# TestBoard3.net
KiCad netlist of a schematic drawn in EAGLE
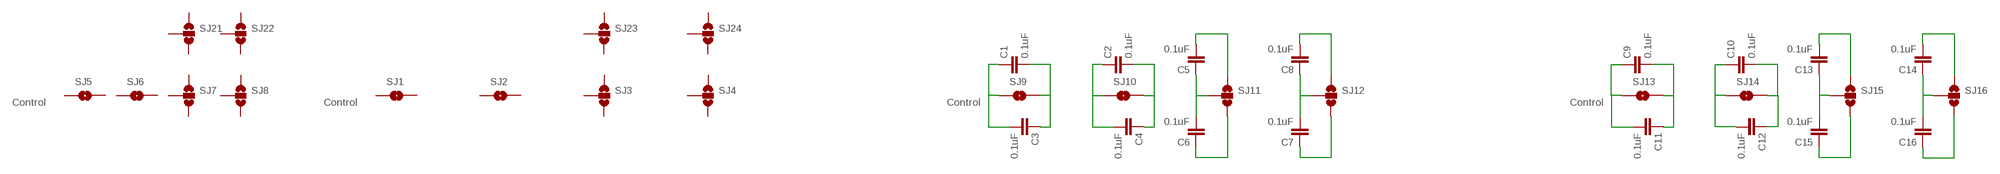
[diagram p0: schematic, sheet 1, part 1 of 3]
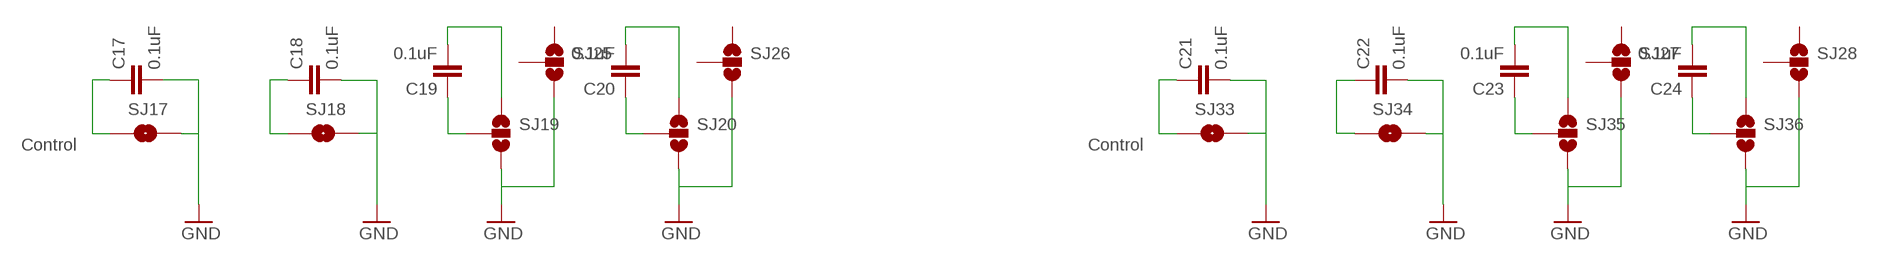
[diagram p1: schematic, sheet 1, part 2 of 3]
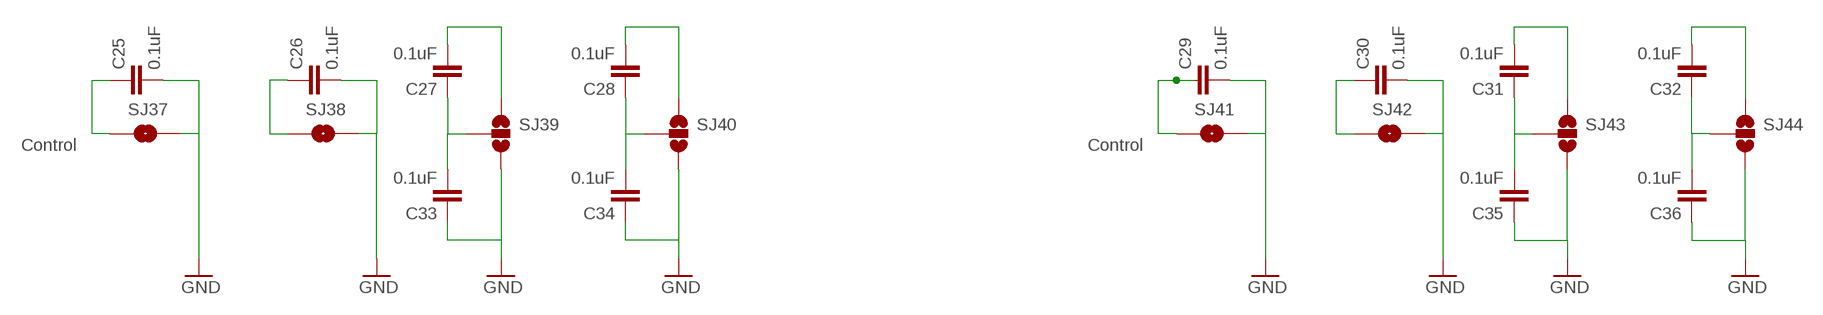
[diagram p2: schematic, sheet 1, part 3 of 3]

(export (version "E")
  (design (tool "Eeschema 10.0.6"))
  (components
    (comp (ref "C1")
      (value "0.1uF")
      (footprint "eagle-import:0603-CAP")
      (libsource (lib "eagle-import") (part "0.1UF-25V-5%(0603)"))
    )
    (comp (ref "C2")
      (value "0.1uF")
      (footprint "eagle-import:0603-CAP")
      (libsource (lib "eagle-import") (part "0.1UF-25V-5%(0603)"))
    )
    (comp (ref "C3")
      (value "0.1uF")
      (footprint "eagle-import:0603-CAP")
      (libsource (lib "eagle-import") (part "0.1UF-25V-5%(0603)"))
    )
    (comp (ref "C4")
      (value "0.1uF")
      (footprint "eagle-import:0603-CAP")
      (libsource (lib "eagle-import") (part "0.1UF-25V-5%(0603)"))
    )
    (comp (ref "C5")
      (value "0.1uF")
      (footprint "eagle-import:0603-CAP")
      (libsource (lib "eagle-import") (part "0.1UF-25V-5%(0603)"))
    )
    (comp (ref "C6")
      (value "0.1uF")
      (footprint "eagle-import:0603-CAP")
      (libsource (lib "eagle-import") (part "0.1UF-25V-5%(0603)"))
    )
    (comp (ref "C7")
      (value "0.1uF")
      (footprint "eagle-import:0603-CAP")
      (libsource (lib "eagle-import") (part "0.1UF-25V-5%(0603)"))
    )
    (comp (ref "C8")
      (value "0.1uF")
      (footprint "eagle-import:0603-CAP")
      (libsource (lib "eagle-import") (part "0.1UF-25V-5%(0603)"))
    )
    (comp (ref "C9")
      (value "0.1uF")
      (footprint "eagle-import:0603-CAP")
      (libsource (lib "eagle-import") (part "0.1UF-25V-5%(0603)"))
    )
    (comp (ref "C10")
      (value "0.1uF")
      (footprint "eagle-import:0603-CAP")
      (libsource (lib "eagle-import") (part "0.1UF-25V-5%(0603)"))
    )
    (comp (ref "C11")
      (value "0.1uF")
      (footprint "eagle-import:0603-CAP")
      (libsource (lib "eagle-import") (part "0.1UF-25V-5%(0603)"))
    )
    (comp (ref "C12")
      (value "0.1uF")
      (footprint "eagle-import:0603-CAP")
      (libsource (lib "eagle-import") (part "0.1UF-25V-5%(0603)"))
    )
    (comp (ref "C13")
      (value "0.1uF")
      (footprint "eagle-import:0603-CAP")
      (libsource (lib "eagle-import") (part "0.1UF-25V-5%(0603)"))
    )
    (comp (ref "C14")
      (value "0.1uF")
      (footprint "eagle-import:0603-CAP")
      (libsource (lib "eagle-import") (part "0.1UF-25V-5%(0603)"))
    )
    (comp (ref "C15")
      (value "0.1uF")
      (footprint "eagle-import:0603-CAP")
      (libsource (lib "eagle-import") (part "0.1UF-25V-5%(0603)"))
    )
    (comp (ref "C16")
      (value "0.1uF")
      (footprint "eagle-import:0603-CAP")
      (libsource (lib "eagle-import") (part "0.1UF-25V-5%(0603)"))
    )
    (comp (ref "C17")
      (value "0.1uF")
      (footprint "eagle-import:0603-CAP")
      (libsource (lib "eagle-import") (part "0.1UF-25V-5%(0603)"))
    )
    (comp (ref "C18")
      (value "0.1uF")
      (footprint "eagle-import:0603-CAP")
      (libsource (lib "eagle-import") (part "0.1UF-25V-5%(0603)"))
    )
    (comp (ref "C19")
      (value "0.1uF")
      (footprint "eagle-import:0603-CAP")
      (libsource (lib "eagle-import") (part "0.1UF-25V-5%(0603)"))
    )
    (comp (ref "C20")
      (value "0.1uF")
      (footprint "eagle-import:0603-CAP")
      (libsource (lib "eagle-import") (part "0.1UF-25V-5%(0603)"))
    )
    (comp (ref "C21")
      (value "0.1uF")
      (footprint "eagle-import:0603-CAP")
      (libsource (lib "eagle-import") (part "0.1UF-25V-5%(0603)"))
    )
    (comp (ref "C22")
      (value "0.1uF")
      (footprint "eagle-import:0603-CAP")
      (libsource (lib "eagle-import") (part "0.1UF-25V-5%(0603)"))
    )
    (comp (ref "C23")
      (value "0.1uF")
      (footprint "eagle-import:0603-CAP")
      (libsource (lib "eagle-import") (part "0.1UF-25V-5%(0603)"))
    )
    (comp (ref "C24")
      (value "0.1uF")
      (footprint "eagle-import:0603-CAP")
      (libsource (lib "eagle-import") (part "0.1UF-25V-5%(0603)"))
    )
    (comp (ref "C25")
      (value "0.1uF")
      (footprint "eagle-import:0603-CAP")
      (libsource (lib "eagle-import") (part "0.1UF-25V-5%(0603)"))
    )
    (comp (ref "C26")
      (value "0.1uF")
      (footprint "eagle-import:0603-CAP")
      (libsource (lib "eagle-import") (part "0.1UF-25V-5%(0603)"))
    )
    (comp (ref "C27")
      (value "0.1uF")
      (footprint "eagle-import:0603-CAP")
      (libsource (lib "eagle-import") (part "0.1UF-25V-5%(0603)"))
    )
    (comp (ref "C28")
      (value "0.1uF")
      (footprint "eagle-import:0603-CAP")
      (libsource (lib "eagle-import") (part "0.1UF-25V-5%(0603)"))
    )
    (comp (ref "C29")
      (value "0.1uF")
      (footprint "eagle-import:0603-CAP")
      (libsource (lib "eagle-import") (part "0.1UF-25V-5%(0603)"))
    )
    (comp (ref "C30")
      (value "0.1uF")
      (footprint "eagle-import:0603-CAP")
      (libsource (lib "eagle-import") (part "0.1UF-25V-5%(0603)"))
    )
    (comp (ref "C31")
      (value "0.1uF")
      (footprint "eagle-import:0603-CAP")
      (libsource (lib "eagle-import") (part "0.1UF-25V-5%(0603)"))
    )
    (comp (ref "C32")
      (value "0.1uF")
      (footprint "eagle-import:0603-CAP")
      (libsource (lib "eagle-import") (part "0.1UF-25V-5%(0603)"))
    )
    (comp (ref "C33")
      (value "0.1uF")
      (footprint "eagle-import:0603-CAP")
      (libsource (lib "eagle-import") (part "0.1UF-25V-5%(0603)"))
    )
    (comp (ref "C34")
      (value "0.1uF")
      (footprint "eagle-import:0603-CAP")
      (libsource (lib "eagle-import") (part "0.1UF-25V-5%(0603)"))
    )
    (comp (ref "C35")
      (value "0.1uF")
      (footprint "eagle-import:0603-CAP")
      (libsource (lib "eagle-import") (part "0.1UF-25V-5%(0603)"))
    )
    (comp (ref "C36")
      (value "0.1uF")
      (footprint "eagle-import:0603-CAP")
      (libsource (lib "eagle-import") (part "0.1UF-25V-5%(0603)"))
    )
    (comp (ref "SJ1")
      (value "JUMPER-PAD-2-NO")
      (footprint "eagle-import:PAD-JUMPER-2-NO_NO_SILK")
      (libsource (lib "eagle-import") (part "JUMPER-PAD-2-NO"))
    )
    (comp (ref "SJ2")
      (value "JUMPER-PAD-2-NO")
      (footprint "eagle-import:PAD-JUMPER-2-NO_NO_SILK")
      (libsource (lib "eagle-import") (part "JUMPER-PAD-2-NO"))
    )
    (comp (ref "SJ3")
      (value "JUMPER-PAD-3-NOYES_SILK")
      (footprint "eagle-import:PAD-JUMPER-3-NO_YES_SILK")
      (libsource (lib "eagle-import") (part "JUMPER-PAD-3-NOYES_SILK"))
    )
    (comp (ref "SJ4")
      (value "JUMPER-PAD-3-NOYES_SILK")
      (footprint "eagle-import:PAD-JUMPER-3-NO_YES_SILK")
      (libsource (lib "eagle-import") (part "JUMPER-PAD-3-NOYES_SILK"))
    )
    (comp (ref "SJ5")
      (value "JUMPER-PAD-2-NO")
      (footprint "eagle-import:PAD-JUMPER-2-NO_NO_SILK")
      (libsource (lib "eagle-import") (part "JUMPER-PAD-2-NO"))
    )
    (comp (ref "SJ6")
      (value "JUMPER-PAD-2-NO")
      (footprint "eagle-import:PAD-JUMPER-2-NO_NO_SILK")
      (libsource (lib "eagle-import") (part "JUMPER-PAD-2-NO"))
    )
    (comp (ref "SJ7")
      (value "JUMPER-PAD-3-NOYES_SILK")
      (footprint "eagle-import:PAD-JUMPER-3-NO_YES_SILK")
      (libsource (lib "eagle-import") (part "JUMPER-PAD-3-NOYES_SILK"))
    )
    (comp (ref "SJ8")
      (value "JUMPER-PAD-3-NOYES_SILK")
      (footprint "eagle-import:PAD-JUMPER-3-NO_YES_SILK")
      (libsource (lib "eagle-import") (part "JUMPER-PAD-3-NOYES_SILK"))
    )
    (comp (ref "SJ9")
      (value "JUMPER-PAD-2-NO")
      (footprint "eagle-import:PAD-JUMPER-2-NO_NO_SILK")
      (libsource (lib "eagle-import") (part "JUMPER-PAD-2-NO"))
    )
    (comp (ref "SJ10")
      (value "JUMPER-PAD-2-NO")
      (footprint "eagle-import:PAD-JUMPER-2-NO_NO_SILK")
      (libsource (lib "eagle-import") (part "JUMPER-PAD-2-NO"))
    )
    (comp (ref "SJ11")
      (value "JUMPER-PAD-3-NOYES_SILK")
      (footprint "eagle-import:PAD-JUMPER-3-NO_YES_SILK")
      (libsource (lib "eagle-import") (part "JUMPER-PAD-3-NOYES_SILK"))
    )
    (comp (ref "SJ12")
      (value "JUMPER-PAD-3-NOYES_SILK")
      (footprint "eagle-import:PAD-JUMPER-3-NO_YES_SILK")
      (libsource (lib "eagle-import") (part "JUMPER-PAD-3-NOYES_SILK"))
    )
    (comp (ref "SJ13")
      (value "JUMPER-PAD-2-NO")
      (footprint "eagle-import:PAD-JUMPER-2-NO_NO_SILK")
      (libsource (lib "eagle-import") (part "JUMPER-PAD-2-NO"))
    )
    (comp (ref "SJ14")
      (value "JUMPER-PAD-2-NO")
      (footprint "eagle-import:PAD-JUMPER-2-NO_NO_SILK")
      (libsource (lib "eagle-import") (part "JUMPER-PAD-2-NO"))
    )
    (comp (ref "SJ15")
      (value "JUMPER-PAD-3-NOYES_SILK")
      (footprint "eagle-import:PAD-JUMPER-3-NO_YES_SILK")
      (libsource (lib "eagle-import") (part "JUMPER-PAD-3-NOYES_SILK"))
    )
    (comp (ref "SJ16")
      (value "JUMPER-PAD-3-NOYES_SILK")
      (footprint "eagle-import:PAD-JUMPER-3-NO_YES_SILK")
      (libsource (lib "eagle-import") (part "JUMPER-PAD-3-NOYES_SILK"))
    )
    (comp (ref "SJ17")
      (value "JUMPER-PAD-2-NO")
      (footprint "eagle-import:PAD-JUMPER-2-NO_NO_SILK")
      (libsource (lib "eagle-import") (part "JUMPER-PAD-2-NO"))
    )
    (comp (ref "SJ18")
      (value "JUMPER-PAD-2-NO")
      (footprint "eagle-import:PAD-JUMPER-2-NO_NO_SILK")
      (libsource (lib "eagle-import") (part "JUMPER-PAD-2-NO"))
    )
    (comp (ref "SJ19")
      (value "JUMPER-PAD-3-NOYES_SILK")
      (footprint "eagle-import:PAD-JUMPER-3-NO_YES_SILK")
      (libsource (lib "eagle-import") (part "JUMPER-PAD-3-NOYES_SILK"))
    )
    (comp (ref "SJ20")
      (value "JUMPER-PAD-3-NOYES_SILK")
      (footprint "eagle-import:PAD-JUMPER-3-NO_YES_SILK")
      (libsource (lib "eagle-import") (part "JUMPER-PAD-3-NOYES_SILK"))
    )
    (comp (ref "SJ21")
      (value "JUMPER-PAD-3-NOYES_SILK")
      (footprint "eagle-import:PAD-JUMPER-3-NO_YES_SILK")
      (libsource (lib "eagle-import") (part "JUMPER-PAD-3-NOYES_SILK"))
    )
    (comp (ref "SJ22")
      (value "JUMPER-PAD-3-NOYES_SILK")
      (footprint "eagle-import:PAD-JUMPER-3-NO_YES_SILK")
      (libsource (lib "eagle-import") (part "JUMPER-PAD-3-NOYES_SILK"))
    )
    (comp (ref "SJ23")
      (value "JUMPER-PAD-3-NOYES_SILK")
      (footprint "eagle-import:PAD-JUMPER-3-NO_YES_SILK")
      (libsource (lib "eagle-import") (part "JUMPER-PAD-3-NOYES_SILK"))
    )
    (comp (ref "SJ24")
      (value "JUMPER-PAD-3-NOYES_SILK")
      (footprint "eagle-import:PAD-JUMPER-3-NO_YES_SILK")
      (libsource (lib "eagle-import") (part "JUMPER-PAD-3-NOYES_SILK"))
    )
    (comp (ref "SJ25")
      (value "JUMPER-PAD-3-NOYES_SILK")
      (footprint "eagle-import:PAD-JUMPER-3-NO_YES_SILK")
      (libsource (lib "eagle-import") (part "JUMPER-PAD-3-NOYES_SILK"))
    )
    (comp (ref "SJ26")
      (value "JUMPER-PAD-3-NOYES_SILK")
      (footprint "eagle-import:PAD-JUMPER-3-NO_YES_SILK")
      (libsource (lib "eagle-import") (part "JUMPER-PAD-3-NOYES_SILK"))
    )
    (comp (ref "SJ27")
      (value "JUMPER-PAD-3-NOYES_SILK")
      (footprint "eagle-import:PAD-JUMPER-3-NO_YES_SILK")
      (libsource (lib "eagle-import") (part "JUMPER-PAD-3-NOYES_SILK"))
    )
    (comp (ref "SJ28")
      (value "JUMPER-PAD-3-NOYES_SILK")
      (footprint "eagle-import:PAD-JUMPER-3-NO_YES_SILK")
      (libsource (lib "eagle-import") (part "JUMPER-PAD-3-NOYES_SILK"))
    )
    (comp (ref "SJ33")
      (value "JUMPER-PAD-2-NO")
      (footprint "eagle-import:PAD-JUMPER-2-NO_NO_SILK")
      (libsource (lib "eagle-import") (part "JUMPER-PAD-2-NO"))
    )
    (comp (ref "SJ34")
      (value "JUMPER-PAD-2-NO")
      (footprint "eagle-import:PAD-JUMPER-2-NO_NO_SILK")
      (libsource (lib "eagle-import") (part "JUMPER-PAD-2-NO"))
    )
    (comp (ref "SJ35")
      (value "JUMPER-PAD-3-NOYES_SILK")
      (footprint "eagle-import:PAD-JUMPER-3-NO_YES_SILK")
      (libsource (lib "eagle-import") (part "JUMPER-PAD-3-NOYES_SILK"))
    )
    (comp (ref "SJ36")
      (value "JUMPER-PAD-3-NOYES_SILK")
      (footprint "eagle-import:PAD-JUMPER-3-NO_YES_SILK")
      (libsource (lib "eagle-import") (part "JUMPER-PAD-3-NOYES_SILK"))
    )
    (comp (ref "SJ37")
      (value "JUMPER-PAD-2-NO")
      (footprint "eagle-import:PAD-JUMPER-2-NO_NO_SILK")
      (libsource (lib "eagle-import") (part "JUMPER-PAD-2-NO"))
    )
    (comp (ref "SJ38")
      (value "JUMPER-PAD-2-NO")
      (footprint "eagle-import:PAD-JUMPER-2-NO_NO_SILK")
      (libsource (lib "eagle-import") (part "JUMPER-PAD-2-NO"))
    )
    (comp (ref "SJ39")
      (value "JUMPER-PAD-3-NOYES_SILK")
      (footprint "eagle-import:PAD-JUMPER-3-NO_YES_SILK")
      (libsource (lib "eagle-import") (part "JUMPER-PAD-3-NOYES_SILK"))
    )
    (comp (ref "SJ40")
      (value "JUMPER-PAD-3-NOYES_SILK")
      (footprint "eagle-import:PAD-JUMPER-3-NO_YES_SILK")
      (libsource (lib "eagle-import") (part "JUMPER-PAD-3-NOYES_SILK"))
    )
    (comp (ref "SJ41")
      (value "JUMPER-PAD-2-NO")
      (footprint "eagle-import:PAD-JUMPER-2-NO_NO_SILK")
      (libsource (lib "eagle-import") (part "JUMPER-PAD-2-NO"))
    )
    (comp (ref "SJ42")
      (value "JUMPER-PAD-2-NO")
      (footprint "eagle-import:PAD-JUMPER-2-NO_NO_SILK")
      (libsource (lib "eagle-import") (part "JUMPER-PAD-2-NO"))
    )
    (comp (ref "SJ43")
      (value "JUMPER-PAD-3-NOYES_SILK")
      (footprint "eagle-import:PAD-JUMPER-3-NO_YES_SILK")
      (libsource (lib "eagle-import") (part "JUMPER-PAD-3-NOYES_SILK"))
    )
    (comp (ref "SJ44")
      (value "JUMPER-PAD-3-NOYES_SILK")
      (footprint "eagle-import:PAD-JUMPER-3-NO_YES_SILK")
      (libsource (lib "eagle-import") (part "JUMPER-PAD-3-NOYES_SILK"))
    )
  )
  (nets
    (net (code "1") (name "GND") (class "Default")
      (node (ref "C17") (pin "2") (pinfunction "2_2") (pintype "passive"))
      (node (ref "C18") (pin "2") (pinfunction "2_2") (pintype "passive"))
      (node (ref "C21") (pin "2") (pinfunction "2_2") (pintype "passive"))
      (node (ref "C22") (pin "2") (pinfunction "2_2") (pintype "passive"))
      (node (ref "C25") (pin "2") (pinfunction "2_2") (pintype "passive"))
      (node (ref "C26") (pin "2") (pinfunction "2_2") (pintype "passive"))
      (node (ref "C29") (pin "2") (pinfunction "2_2") (pintype "passive"))
      (node (ref "C30") (pin "2") (pinfunction "2_2") (pintype "passive"))
      (node (ref "C33") (pin "1") (pinfunction "1_1") (pintype "passive"))
      (node (ref "C34") (pin "1") (pinfunction "1_1") (pintype "passive"))
      (node (ref "C35") (pin "1") (pinfunction "1_1") (pintype "passive"))
      (node (ref "C36") (pin "1") (pinfunction "1_1") (pintype "passive"))
      (node (ref "SJ17") (pin "2") (pinfunction "2_2") (pintype "passive"))
      (node (ref "SJ18") (pin "2") (pinfunction "2_2") (pintype "passive"))
      (node (ref "SJ19") (pin "3") (pinfunction "3_3") (pintype "passive"))
      (node (ref "SJ20") (pin "3") (pinfunction "3_3") (pintype "passive"))
      (node (ref "SJ25") (pin "3") (pinfunction "3_3") (pintype "passive"))
      (node (ref "SJ26") (pin "3") (pinfunction "3_3") (pintype "passive"))
      (node (ref "SJ27") (pin "3") (pinfunction "3_3") (pintype "passive"))
      (node (ref "SJ28") (pin "3") (pinfunction "3_3") (pintype "passive"))
      (node (ref "SJ33") (pin "2") (pinfunction "2_2") (pintype "passive"))
      (node (ref "SJ34") (pin "2") (pinfunction "2_2") (pintype "passive"))
      (node (ref "SJ35") (pin "3") (pinfunction "3_3") (pintype "passive"))
      (node (ref "SJ36") (pin "3") (pinfunction "3_3") (pintype "passive"))
      (node (ref "SJ37") (pin "2") (pinfunction "2_2") (pintype "passive"))
      (node (ref "SJ38") (pin "2") (pinfunction "2_2") (pintype "passive"))
      (node (ref "SJ39") (pin "3") (pinfunction "3_3") (pintype "passive"))
      (node (ref "SJ40") (pin "3") (pinfunction "3_3") (pintype "passive"))
      (node (ref "SJ41") (pin "2") (pinfunction "2_2") (pintype "passive"))
      (node (ref "SJ42") (pin "2") (pinfunction "2_2") (pintype "passive"))
      (node (ref "SJ43") (pin "3") (pinfunction "3_3") (pintype "passive"))
      (node (ref "SJ44") (pin "3") (pinfunction "3_3") (pintype "passive"))
    )
    (net (code "2") (name "Net-(C1-Pad1)") (class "Default")
      (node (ref "C1") (pin "1") (pinfunction "1_1") (pintype "passive"))
      (node (ref "C3") (pin "2") (pinfunction "2_2") (pintype "passive"))
      (node (ref "SJ9") (pin "1") (pinfunction "1_1") (pintype "passive"))
    )
    (net (code "3") (name "Net-(C1-Pad2)") (class "Default")
      (node (ref "C1") (pin "2") (pinfunction "2_2") (pintype "passive"))
      (node (ref "C3") (pin "1") (pinfunction "1_1") (pintype "passive"))
      (node (ref "SJ9") (pin "2") (pinfunction "2_2") (pintype "passive"))
    )
    (net (code "4") (name "Net-(C2-Pad1)") (class "Default")
      (node (ref "C2") (pin "1") (pinfunction "1_1") (pintype "passive"))
      (node (ref "C4") (pin "2") (pinfunction "2_2") (pintype "passive"))
      (node (ref "SJ10") (pin "1") (pinfunction "1_1") (pintype "passive"))
    )
    (net (code "5") (name "Net-(C2-Pad2)") (class "Default")
      (node (ref "C2") (pin "2") (pinfunction "2_2") (pintype "passive"))
      (node (ref "C4") (pin "1") (pinfunction "1_1") (pintype "passive"))
      (node (ref "SJ10") (pin "2") (pinfunction "2_2") (pintype "passive"))
    )
    (net (code "6") (name "Net-(C5-Pad1)") (class "Default")
      (node (ref "C5") (pin "1") (pinfunction "1_1") (pintype "passive"))
      (node (ref "C6") (pin "2") (pinfunction "2_2") (pintype "passive"))
      (node (ref "SJ11") (pin "2") (pinfunction "2_2") (pintype "passive"))
    )
    (net (code "7") (name "Net-(C5-Pad2)") (class "Default")
      (node (ref "C5") (pin "2") (pinfunction "2_2") (pintype "passive"))
      (node (ref "SJ11") (pin "1") (pinfunction "1_1") (pintype "passive"))
    )
    (net (code "8") (name "Net-(C6-Pad1)") (class "Default")
      (node (ref "C6") (pin "1") (pinfunction "1_1") (pintype "passive"))
      (node (ref "SJ11") (pin "3") (pinfunction "3_3") (pintype "passive"))
    )
    (net (code "9") (name "Net-(C7-Pad1)") (class "Default")
      (node (ref "C7") (pin "1") (pinfunction "1_1") (pintype "passive"))
      (node (ref "SJ12") (pin "3") (pinfunction "3_3") (pintype "passive"))
    )
    (net (code "10") (name "Net-(C7-Pad2)") (class "Default")
      (node (ref "C7") (pin "2") (pinfunction "2_2") (pintype "passive"))
      (node (ref "C8") (pin "1") (pinfunction "1_1") (pintype "passive"))
      (node (ref "SJ12") (pin "2") (pinfunction "2_2") (pintype "passive"))
    )
    (net (code "11") (name "Net-(C8-Pad2)") (class "Default")
      (node (ref "C8") (pin "2") (pinfunction "2_2") (pintype "passive"))
      (node (ref "SJ12") (pin "1") (pinfunction "1_1") (pintype "passive"))
    )
    (net (code "12") (name "Net-(C10-Pad1)") (class "Default")
      (node (ref "C10") (pin "1") (pinfunction "1_1") (pintype "passive"))
      (node (ref "C12") (pin "2") (pinfunction "2_2") (pintype "passive"))
      (node (ref "SJ14") (pin "1") (pinfunction "1_1") (pintype "passive"))
    )
    (net (code "13") (name "Net-(C10-Pad2)") (class "Default")
      (node (ref "C10") (pin "2") (pinfunction "2_2") (pintype "passive"))
      (node (ref "C12") (pin "1") (pinfunction "1_1") (pintype "passive"))
      (node (ref "SJ14") (pin "2") (pinfunction "2_2") (pintype "passive"))
    )
    (net (code "14") (name "Net-(C11-Pad1)") (class "Default")
      (node (ref "C11") (pin "1") (pinfunction "1_1") (pintype "passive"))
      (node (ref "C9") (pin "2") (pinfunction "2_2") (pintype "passive"))
      (node (ref "SJ13") (pin "2") (pinfunction "2_2") (pintype "passive"))
    )
    (net (code "15") (name "Net-(C11-Pad2)") (class "Default")
      (node (ref "C11") (pin "2") (pinfunction "2_2") (pintype "passive"))
      (node (ref "C9") (pin "1") (pinfunction "1_1") (pintype "passive"))
      (node (ref "SJ13") (pin "1") (pinfunction "1_1") (pintype "passive"))
    )
    (net (code "16") (name "Net-(C13-Pad1)") (class "Default")
      (node (ref "C13") (pin "1") (pinfunction "1_1") (pintype "passive"))
      (node (ref "C15") (pin "2") (pinfunction "2_2") (pintype "passive"))
      (node (ref "SJ15") (pin "2") (pinfunction "2_2") (pintype "passive"))
    )
    (net (code "17") (name "Net-(C13-Pad2)") (class "Default")
      (node (ref "C13") (pin "2") (pinfunction "2_2") (pintype "passive"))
      (node (ref "SJ15") (pin "1") (pinfunction "1_1") (pintype "passive"))
    )
    (net (code "18") (name "Net-(C14-Pad1)") (class "Default")
      (node (ref "C14") (pin "1") (pinfunction "1_1") (pintype "passive"))
      (node (ref "C16") (pin "2") (pinfunction "2_2") (pintype "passive"))
      (node (ref "SJ16") (pin "2") (pinfunction "2_2") (pintype "passive"))
    )
    (net (code "19") (name "Net-(C14-Pad2)") (class "Default")
      (node (ref "C14") (pin "2") (pinfunction "2_2") (pintype "passive"))
      (node (ref "SJ16") (pin "1") (pinfunction "1_1") (pintype "passive"))
    )
    (net (code "20") (name "Net-(C15-Pad1)") (class "Default")
      (node (ref "C15") (pin "1") (pinfunction "1_1") (pintype "passive"))
      (node (ref "SJ15") (pin "3") (pinfunction "3_3") (pintype "passive"))
    )
    (net (code "21") (name "Net-(C16-Pad1)") (class "Default")
      (node (ref "C16") (pin "1") (pinfunction "1_1") (pintype "passive"))
      (node (ref "SJ16") (pin "3") (pinfunction "3_3") (pintype "passive"))
    )
    (net (code "22") (name "Net-(C17-Pad1)") (class "Default")
      (node (ref "C17") (pin "1") (pinfunction "1_1") (pintype "passive"))
      (node (ref "SJ17") (pin "1") (pinfunction "1_1") (pintype "passive"))
    )
    (net (code "23") (name "Net-(C18-Pad1)") (class "Default")
      (node (ref "C18") (pin "1") (pinfunction "1_1") (pintype "passive"))
      (node (ref "SJ18") (pin "1") (pinfunction "1_1") (pintype "passive"))
    )
    (net (code "24") (name "Net-(C19-Pad1)") (class "Default")
      (node (ref "C19") (pin "1") (pinfunction "1_1") (pintype "passive"))
      (node (ref "SJ19") (pin "2") (pinfunction "2_2") (pintype "passive"))
    )
    (net (code "25") (name "Net-(C19-Pad2)") (class "Default")
      (node (ref "C19") (pin "2") (pinfunction "2_2") (pintype "passive"))
      (node (ref "SJ19") (pin "1") (pinfunction "1_1") (pintype "passive"))
    )
    (net (code "26") (name "Net-(C20-Pad1)") (class "Default")
      (node (ref "C20") (pin "1") (pinfunction "1_1") (pintype "passive"))
      (node (ref "SJ20") (pin "2") (pinfunction "2_2") (pintype "passive"))
    )
    (net (code "27") (name "Net-(C20-Pad2)") (class "Default")
      (node (ref "C20") (pin "2") (pinfunction "2_2") (pintype "passive"))
      (node (ref "SJ20") (pin "1") (pinfunction "1_1") (pintype "passive"))
    )
    (net (code "28") (name "Net-(C21-Pad1)") (class "Default")
      (node (ref "C21") (pin "1") (pinfunction "1_1") (pintype "passive"))
      (node (ref "SJ33") (pin "1") (pinfunction "1_1") (pintype "passive"))
    )
    (net (code "29") (name "Net-(C22-Pad1)") (class "Default")
      (node (ref "C22") (pin "1") (pinfunction "1_1") (pintype "passive"))
      (node (ref "SJ34") (pin "1") (pinfunction "1_1") (pintype "passive"))
    )
    (net (code "30") (name "Net-(C23-Pad1)") (class "Default")
      (node (ref "C23") (pin "1") (pinfunction "1_1") (pintype "passive"))
      (node (ref "SJ35") (pin "2") (pinfunction "2_2") (pintype "passive"))
    )
    (net (code "31") (name "Net-(C23-Pad2)") (class "Default")
      (node (ref "C23") (pin "2") (pinfunction "2_2") (pintype "passive"))
      (node (ref "SJ35") (pin "1") (pinfunction "1_1") (pintype "passive"))
    )
    (net (code "32") (name "Net-(C24-Pad1)") (class "Default")
      (node (ref "C24") (pin "1") (pinfunction "1_1") (pintype "passive"))
      (node (ref "SJ36") (pin "2") (pinfunction "2_2") (pintype "passive"))
    )
    (net (code "33") (name "Net-(C24-Pad2)") (class "Default")
      (node (ref "C24") (pin "2") (pinfunction "2_2") (pintype "passive"))
      (node (ref "SJ36") (pin "1") (pinfunction "1_1") (pintype "passive"))
    )
    (net (code "34") (name "Net-(C25-Pad1)") (class "Default")
      (node (ref "C25") (pin "1") (pinfunction "1_1") (pintype "passive"))
      (node (ref "SJ37") (pin "1") (pinfunction "1_1") (pintype "passive"))
    )
    (net (code "35") (name "Net-(C26-Pad1)") (class "Default")
      (node (ref "C26") (pin "1") (pinfunction "1_1") (pintype "passive"))
      (node (ref "SJ38") (pin "1") (pinfunction "1_1") (pintype "passive"))
    )
    (net (code "36") (name "Net-(C27-Pad1)") (class "Default")
      (node (ref "C27") (pin "1") (pinfunction "1_1") (pintype "passive"))
      (node (ref "C33") (pin "2") (pinfunction "2_2") (pintype "passive"))
      (node (ref "SJ39") (pin "2") (pinfunction "2_2") (pintype "passive"))
    )
    (net (code "37") (name "Net-(C27-Pad2)") (class "Default")
      (node (ref "C27") (pin "2") (pinfunction "2_2") (pintype "passive"))
      (node (ref "SJ39") (pin "1") (pinfunction "1_1") (pintype "passive"))
    )
    (net (code "38") (name "Net-(C28-Pad1)") (class "Default")
      (node (ref "C28") (pin "1") (pinfunction "1_1") (pintype "passive"))
      (node (ref "C34") (pin "2") (pinfunction "2_2") (pintype "passive"))
      (node (ref "SJ40") (pin "2") (pinfunction "2_2") (pintype "passive"))
    )
    (net (code "39") (name "Net-(C28-Pad2)") (class "Default")
      (node (ref "C28") (pin "2") (pinfunction "2_2") (pintype "passive"))
      (node (ref "SJ40") (pin "1") (pinfunction "1_1") (pintype "passive"))
    )
    (net (code "40") (name "Net-(C29-Pad1)") (class "Default")
      (node (ref "C29") (pin "1") (pinfunction "1_1") (pintype "passive"))
      (node (ref "SJ41") (pin "1") (pinfunction "1_1") (pintype "passive"))
    )
    (net (code "41") (name "Net-(C30-Pad1)") (class "Default")
      (node (ref "C30") (pin "1") (pinfunction "1_1") (pintype "passive"))
      (node (ref "SJ42") (pin "1") (pinfunction "1_1") (pintype "passive"))
    )
    (net (code "42") (name "Net-(C31-Pad1)") (class "Default")
      (node (ref "C31") (pin "1") (pinfunction "1_1") (pintype "passive"))
      (node (ref "C35") (pin "2") (pinfunction "2_2") (pintype "passive"))
      (node (ref "SJ43") (pin "2") (pinfunction "2_2") (pintype "passive"))
    )
    (net (code "43") (name "Net-(C31-Pad2)") (class "Default")
      (node (ref "C31") (pin "2") (pinfunction "2_2") (pintype "passive"))
      (node (ref "SJ43") (pin "1") (pinfunction "1_1") (pintype "passive"))
    )
    (net (code "44") (name "Net-(C32-Pad1)") (class "Default")
      (node (ref "C32") (pin "1") (pinfunction "1_1") (pintype "passive"))
      (node (ref "C36") (pin "2") (pinfunction "2_2") (pintype "passive"))
      (node (ref "SJ44") (pin "2") (pinfunction "2_2") (pintype "passive"))
    )
    (net (code "45") (name "Net-(C32-Pad2)") (class "Default")
      (node (ref "C32") (pin "2") (pinfunction "2_2") (pintype "passive"))
      (node (ref "SJ44") (pin "1") (pinfunction "1_1") (pintype "passive"))
    )
    (net (code "46") (name "unconnected-(SJ1-Pad1)") (class "Default")
      (node (ref "SJ1") (pin "1") (pinfunction "1_1") (pintype "passive"))
    )
    (net (code "47") (name "unconnected-(SJ1-Pad2)") (class "Default")
      (node (ref "SJ1") (pin "2") (pinfunction "2_2") (pintype "passive"))
    )
    (net (code "48") (name "unconnected-(SJ2-Pad1)") (class "Default")
      (node (ref "SJ2") (pin "1") (pinfunction "1_1") (pintype "passive"))
    )
    (net (code "49") (name "unconnected-(SJ2-Pad2)") (class "Default")
      (node (ref "SJ2") (pin "2") (pinfunction "2_2") (pintype "passive"))
    )
    (net (code "50") (name "unconnected-(SJ3-Pad1)") (class "Default")
      (node (ref "SJ3") (pin "1") (pinfunction "1_1") (pintype "passive"))
    )
    (net (code "51") (name "unconnected-(SJ3-Pad2)") (class "Default")
      (node (ref "SJ3") (pin "2") (pinfunction "2_2") (pintype "passive"))
    )
    (net (code "52") (name "unconnected-(SJ3-Pad3)") (class "Default")
      (node (ref "SJ3") (pin "3") (pinfunction "3_3") (pintype "passive"))
    )
    (net (code "53") (name "unconnected-(SJ4-Pad1)") (class "Default")
      (node (ref "SJ4") (pin "1") (pinfunction "1_1") (pintype "passive"))
    )
    (net (code "54") (name "unconnected-(SJ4-Pad2)") (class "Default")
      (node (ref "SJ4") (pin "2") (pinfunction "2_2") (pintype "passive"))
    )
    (net (code "55") (name "unconnected-(SJ4-Pad3)") (class "Default")
      (node (ref "SJ4") (pin "3") (pinfunction "3_3") (pintype "passive"))
    )
    (net (code "56") (name "unconnected-(SJ5-Pad1)") (class "Default")
      (node (ref "SJ5") (pin "1") (pinfunction "1_1") (pintype "passive"))
    )
    (net (code "57") (name "unconnected-(SJ5-Pad2)") (class "Default")
      (node (ref "SJ5") (pin "2") (pinfunction "2_2") (pintype "passive"))
    )
    (net (code "58") (name "unconnected-(SJ6-Pad1)") (class "Default")
      (node (ref "SJ6") (pin "1") (pinfunction "1_1") (pintype "passive"))
    )
    (net (code "59") (name "unconnected-(SJ6-Pad2)") (class "Default")
      (node (ref "SJ6") (pin "2") (pinfunction "2_2") (pintype "passive"))
    )
    (net (code "60") (name "unconnected-(SJ7-Pad1)") (class "Default")
      (node (ref "SJ7") (pin "1") (pinfunction "1_1") (pintype "passive"))
    )
    (net (code "61") (name "unconnected-(SJ7-Pad2)") (class "Default")
      (node (ref "SJ7") (pin "2") (pinfunction "2_2") (pintype "passive"))
    )
    (net (code "62") (name "unconnected-(SJ7-Pad3)") (class "Default")
      (node (ref "SJ7") (pin "3") (pinfunction "3_3") (pintype "passive"))
    )
    (net (code "63") (name "unconnected-(SJ8-Pad1)") (class "Default")
      (node (ref "SJ8") (pin "1") (pinfunction "1_1") (pintype "passive"))
    )
    (net (code "64") (name "unconnected-(SJ8-Pad2)") (class "Default")
      (node (ref "SJ8") (pin "2") (pinfunction "2_2") (pintype "passive"))
    )
    (net (code "65") (name "unconnected-(SJ8-Pad3)") (class "Default")
      (node (ref "SJ8") (pin "3") (pinfunction "3_3") (pintype "passive"))
    )
    (net (code "66") (name "unconnected-(SJ21-Pad1)") (class "Default")
      (node (ref "SJ21") (pin "1") (pinfunction "1_1") (pintype "passive"))
    )
    (net (code "67") (name "unconnected-(SJ21-Pad2)") (class "Default")
      (node (ref "SJ21") (pin "2") (pinfunction "2_2") (pintype "passive"))
    )
    (net (code "68") (name "unconnected-(SJ21-Pad3)") (class "Default")
      (node (ref "SJ21") (pin "3") (pinfunction "3_3") (pintype "passive"))
    )
    (net (code "69") (name "unconnected-(SJ22-Pad1)") (class "Default")
      (node (ref "SJ22") (pin "1") (pinfunction "1_1") (pintype "passive"))
    )
    (net (code "70") (name "unconnected-(SJ22-Pad2)") (class "Default")
      (node (ref "SJ22") (pin "2") (pinfunction "2_2") (pintype "passive"))
    )
    (net (code "71") (name "unconnected-(SJ22-Pad3)") (class "Default")
      (node (ref "SJ22") (pin "3") (pinfunction "3_3") (pintype "passive"))
    )
    (net (code "72") (name "unconnected-(SJ23-Pad1)") (class "Default")
      (node (ref "SJ23") (pin "1") (pinfunction "1_1") (pintype "passive"))
    )
    (net (code "73") (name "unconnected-(SJ23-Pad2)") (class "Default")
      (node (ref "SJ23") (pin "2") (pinfunction "2_2") (pintype "passive"))
    )
    (net (code "74") (name "unconnected-(SJ23-Pad3)") (class "Default")
      (node (ref "SJ23") (pin "3") (pinfunction "3_3") (pintype "passive"))
    )
    (net (code "75") (name "unconnected-(SJ24-Pad1)") (class "Default")
      (node (ref "SJ24") (pin "1") (pinfunction "1_1") (pintype "passive"))
    )
    (net (code "76") (name "unconnected-(SJ24-Pad2)") (class "Default")
      (node (ref "SJ24") (pin "2") (pinfunction "2_2") (pintype "passive"))
    )
    (net (code "77") (name "unconnected-(SJ24-Pad3)") (class "Default")
      (node (ref "SJ24") (pin "3") (pinfunction "3_3") (pintype "passive"))
    )
    (net (code "78") (name "unconnected-(SJ25-Pad1)") (class "Default")
      (node (ref "SJ25") (pin "1") (pinfunction "1_1") (pintype "passive"))
    )
    (net (code "79") (name "unconnected-(SJ25-Pad2)") (class "Default")
      (node (ref "SJ25") (pin "2") (pinfunction "2_2") (pintype "passive"))
    )
    (net (code "80") (name "unconnected-(SJ26-Pad1)") (class "Default")
      (node (ref "SJ26") (pin "1") (pinfunction "1_1") (pintype "passive"))
    )
    (net (code "81") (name "unconnected-(SJ26-Pad2)") (class "Default")
      (node (ref "SJ26") (pin "2") (pinfunction "2_2") (pintype "passive"))
    )
    (net (code "82") (name "unconnected-(SJ27-Pad1)") (class "Default")
      (node (ref "SJ27") (pin "1") (pinfunction "1_1") (pintype "passive"))
    )
    (net (code "83") (name "unconnected-(SJ27-Pad2)") (class "Default")
      (node (ref "SJ27") (pin "2") (pinfunction "2_2") (pintype "passive"))
    )
    (net (code "84") (name "unconnected-(SJ28-Pad1)") (class "Default")
      (node (ref "SJ28") (pin "1") (pinfunction "1_1") (pintype "passive"))
    )
    (net (code "85") (name "unconnected-(SJ28-Pad2)") (class "Default")
      (node (ref "SJ28") (pin "2") (pinfunction "2_2") (pintype "passive"))
    )
  )
)
